# Sheet1.net
KiCad netlist of a schematic drawn in Altium Designer
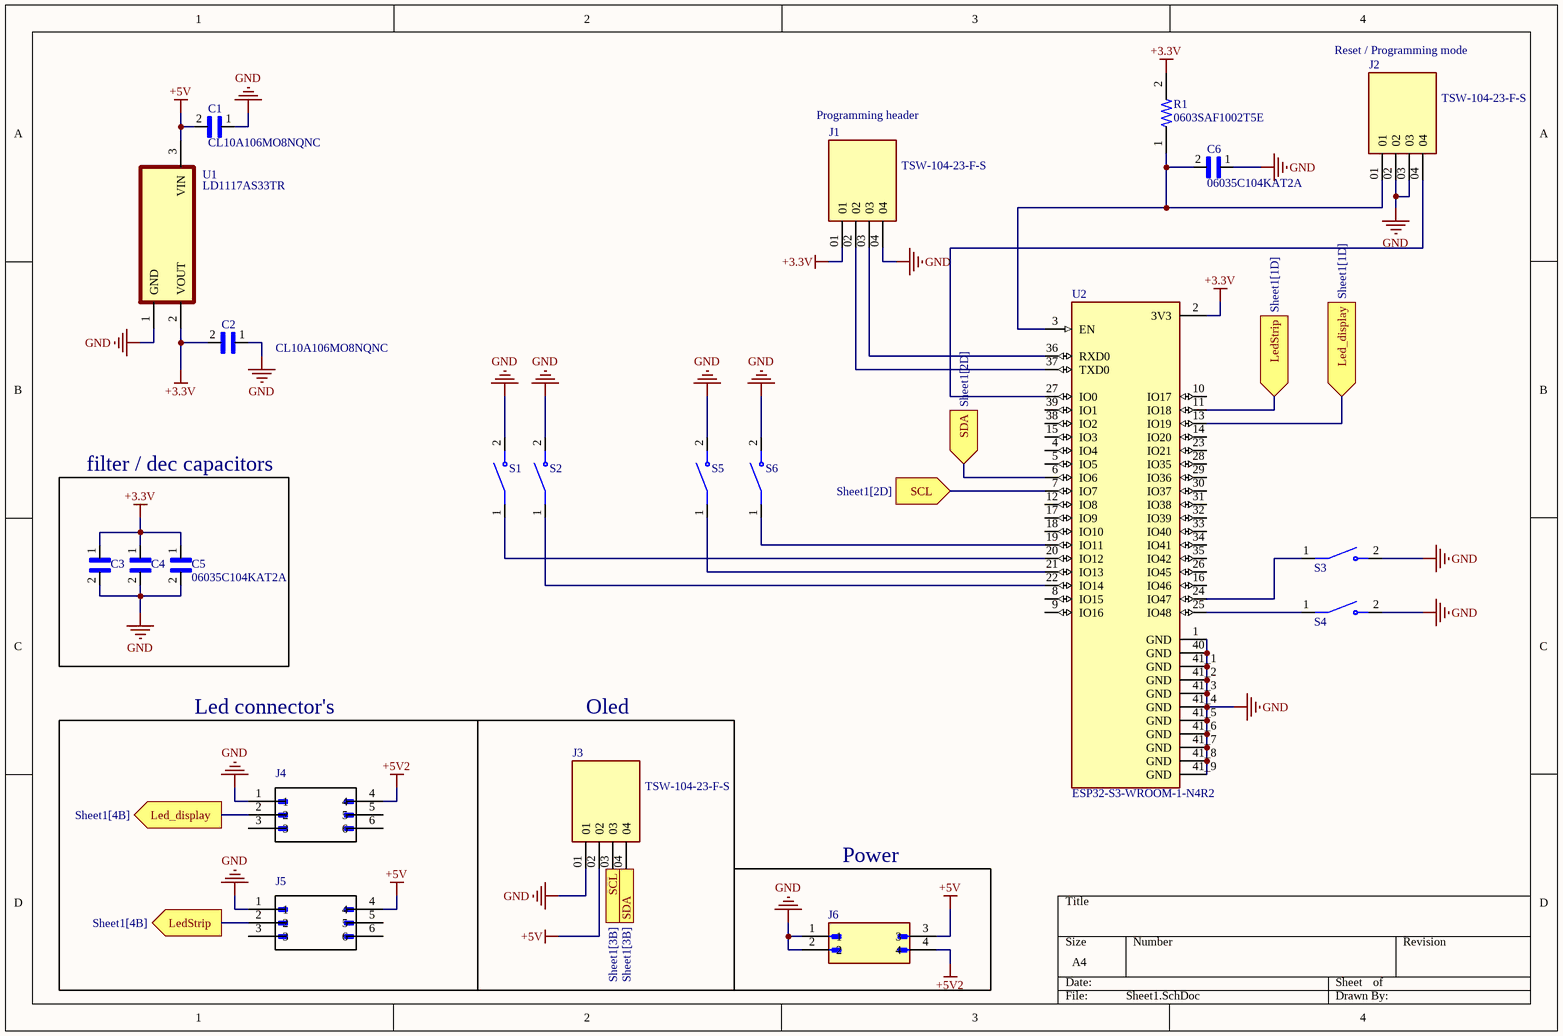
[diagram p0: Sheet1.SchDoc]

(export (version "E")
  (design (tool "Eeschema 10.0.6"))
  (components
    (comp (ref "C1")
      (value "CL10A106MO8NQNC")
      (footprint "CL10A106MO8NQNC:CAPC1608X90N")
      (description "Cap Ceramic 10uF 16V X5R 20% SMD 0603 85Â°C Paper T/R")
      (fields (field (name "MF") "{'manufacturer': u'Samsung Electro-Mechanics'}"))
      (libsource (lib "*") (part "CL10A106MO8NQNC"))
    )
    (comp (ref "C2")
      (value "CL10A106MO8NQNC")
      (footprint "CL10A106MO8NQNC:CAPC1608X90N")
      (description "Cap Ceramic 10uF 16V X5R 20% SMD 0603 85Â°C Paper T/R")
      (fields (field (name "MF") "{'manufacturer': u'Samsung Electro-Mechanics'}"))
      (libsource (lib "*") (part "CL10A106MO8NQNC"))
    )
    (comp (ref "C3")
      (value "06035C104KAT2A")
      (footprint "06035C104KAT2A:CAPC1608X90N")
      (fields (field (name "MF") "{'manufacturer': u'AVX'}"))
      (libsource (lib "*") (part "06035C104KAT2A"))
    )
    (comp (ref "C4")
      (value "06035C104KAT2A")
      (footprint "06035C104KAT2A:CAPC1608X90N")
      (fields (field (name "MF") "{'manufacturer': u'AVX'}"))
      (libsource (lib "*") (part "06035C104KAT2A"))
    )
    (comp (ref "C5")
      (value "06035C104KAT2A")
      (footprint "06035C104KAT2A:CAPC1608X90N")
      (fields (field (name "MF") "{'manufacturer': u'AVX'}"))
      (libsource (lib "*") (part "06035C104KAT2A"))
    )
    (comp (ref "C6")
      (value "06035C104KAT2A")
      (footprint "06035C104KAT2A:CAPC1608X90N")
      (fields (field (name "MF") "{'manufacturer': u'AVX'}"))
      (libsource (lib "") (part "06035C104KAT2A_1"))
    )
    (comp (ref "J1")
      (value "TSW-104-23-F-S")
      (footprint "TSW-104-23-F-S:SAMTEC_TSW-104-23-F-S")
      (fields (field (name "MF") "{'manufacturer': u'Samtec'}"))
      (libsource (lib "*") (part "TSW-104-23-F-S"))
    )
    (comp (ref "J2")
      (value "TSW-104-23-F-S")
      (footprint "TSW-104-23-F-S:SAMTEC_TSW-104-23-F-S")
      (fields (field (name "MF") "{'manufacturer': u'Samtec'}"))
      (libsource (lib "*") (part "TSW-104-23-F-S"))
    )
    (comp (ref "J3")
      (value "TSW-104-23-F-S")
      (footprint "TSW-104-23-F-S:SAMTEC_TSW-104-23-F-S")
      (fields (field (name "MF") "{'manufacturer': u'Samtec'}"))
      (libsource (lib "*") (part "TSW-104-23-F-S"))
    )
    (comp (ref "J4")
      (value "874270602")
      (footprint "*MOLEX_874270602")
      (libsource (lib "874270602") (part "874270602"))
    )
    (comp (ref "J5")
      (value "874270602")
      (footprint "*MOLEX_874270602")
      (libsource (lib "874270602") (part "874270602"))
    )
    (comp (ref "J6")
      (value "353180420")
      (footprint "*MOLEX_353180420")
      (description "Connector Header Through Hole, Right Angle 4 position 0.165in (4.20mm)")
      (fields (field (name "MF") "{'manufacturer': u'Molex'}"))
      (libsource (lib "*") (part "353180420"))
    )
    (comp (ref "R1")
      (value "0603SAF1002T5E")
      (footprint "RP73PF1J10KBTDF:RESC1608X50N")
      (description "0603 10k ohm")
      (fields
        (field (name "MF") "{'manufacturer': u'TE Connectivity'}")
        (field (name "MP") "RP73PF1J10KBTDF")
      )
      (libsource (lib "*") (part "RP73PF1J10KBTDF"))
    )
    (comp (ref "S1")
      (value "TL1107BF130WQ")
      (footprint "SW_MX_reversible")
      (fields (field (name "MF") "{'manufacturer': u'E-Switch'}"))
      (libsource (lib "TL1107BF130WQ") (part "TL1107BF130WQ"))
    )
    (comp (ref "S2")
      (value "TL1107BF130WQ")
      (footprint "SW_MX_reversible")
      (fields (field (name "MF") "{'manufacturer': u'E-Switch'}"))
      (libsource (lib "TL1107BF130WQ") (part "TL1107BF130WQ"))
    )
    (comp (ref "S3")
      (value "TL1107BF130WQ")
      (footprint "SW_MX_reversible")
      (fields (field (name "MF") "{'manufacturer': u'E-Switch'}"))
      (libsource (lib "TL1107BF130WQ") (part "TL1107BF130WQ"))
    )
    (comp (ref "S4")
      (value "TL1107BF130WQ")
      (footprint "SW_MX_reversible")
      (fields (field (name "MF") "{'manufacturer': u'E-Switch'}"))
      (libsource (lib "TL1107BF130WQ") (part "TL1107BF130WQ"))
    )
    (comp (ref "S5")
      (value "TL1107BF130WQ")
      (footprint "SW_MX_reversible")
      (fields (field (name "MF") "{'manufacturer': u'E-Switch'}"))
      (libsource (lib "TL1107BF130WQ") (part "TL1107BF130WQ"))
    )
    (comp (ref "S6")
      (value "TL1107BF130WQ")
      (footprint "SW_MX_reversible")
      (fields (field (name "MF") "{'manufacturer': u'E-Switch'}"))
      (libsource (lib "TL1107BF130WQ") (part "TL1107BF130WQ"))
    )
    (comp (ref "U1")
      (value "LD1117AS33TR")
      (footprint "LD1117AS33TR:SOT230P700X180-4N")
      (fields (field (name "MF") "{'manufacturer': u'STMicroelectronics'}"))
      (libsource (lib "*") (part "LD1117AS33TR"))
    )
    (comp (ref "U2")
      (value "ESP32-S3-WROOM-1-N4R2")
      (footprint "XCVR_ESP32-S3-WROOM-1-N4R2")
      (fields (field (name "MF") "{'manufacturer': u'Espressif Systems'}"))
      (libsource (lib "ESP32-S3-WROOM-1-N4R2") (part "ESP32-S3-WROOM-1-N4R2"))
    )
  )
  (nets
    (net (code "1") (name "+3.3V") (class "Default")
      (node (ref "C2") (pin "2") (pinfunction "2_2") (pintype "passive"))
      (node (ref "C3") (pin "1") (pinfunction "1_1") (pintype "passive"))
      (node (ref "C4") (pin "1") (pinfunction "1_1") (pintype "passive"))
      (node (ref "C5") (pin "1") (pinfunction "1_1") (pintype "passive"))
      (node (ref "J1") (pin "01") (pinfunction "01_01") (pintype "passive"))
      (node (ref "R1") (pin "2") (pinfunction "2_2") (pintype "passive"))
      (node (ref "U1") (pin "2") (pinfunction "VOUT_2") (pintype "power_in"))
      (node (ref "U2") (pin "2") (pinfunction "3V3_2") (pintype "power_in"))
    )
    (net (code "2") (name "+5V") (class "Default")
      (node (ref "C1") (pin "2") (pinfunction "2_2") (pintype "passive"))
      (node (ref "J3") (pin "02") (pinfunction "02_02") (pintype "passive"))
      (node (ref "J5") (pin "4") (pinfunction "4_4") (pintype "passive"))
      (node (ref "J6") (pin "3") (pinfunction "3_3") (pintype "passive"))
      (node (ref "U1") (pin "3") (pinfunction "VIN_3") (pintype "power_in"))
    )
    (net (code "3") (name "+5V2") (class "Default")
      (node (ref "J4") (pin "4") (pinfunction "4_4") (pintype "passive"))
      (node (ref "J6") (pin "4") (pinfunction "4_4") (pintype "passive"))
    )
    (net (code "4") (name "/LedStrip") (class "Default")
      (node (ref "J5") (pin "2") (pinfunction "2_2") (pintype "passive"))
      (node (ref "U2") (pin "11") (pinfunction "IO18_11") (pintype "bidirectional"))
    )
    (net (code "5") (name "/Led_display") (class "Default")
      (node (ref "J4") (pin "2") (pinfunction "2_2") (pintype "passive"))
      (node (ref "U2") (pin "13") (pinfunction "IO19_13") (pintype "bidirectional"))
    )
    (net (code "6") (name "/SCL") (class "Default")
      (node (ref "J3") (pin "03") (pinfunction "03_03") (pintype "passive"))
      (node (ref "U2") (pin "7") (pinfunction "IO7_7") (pintype "bidirectional"))
    )
    (net (code "7") (name "/SDA") (class "Default")
      (node (ref "J3") (pin "04") (pinfunction "04_04") (pintype "passive"))
      (node (ref "U2") (pin "6") (pinfunction "IO6_6") (pintype "bidirectional"))
    )
    (net (code "8") (name "GND") (class "Default")
      (node (ref "C1") (pin "1") (pinfunction "1_1") (pintype "passive"))
      (node (ref "C2") (pin "1") (pinfunction "1_1") (pintype "passive"))
      (node (ref "C3") (pin "2") (pinfunction "2_2") (pintype "passive"))
      (node (ref "C4") (pin "2") (pinfunction "2_2") (pintype "passive"))
      (node (ref "C5") (pin "2") (pinfunction "2_2") (pintype "passive"))
      (node (ref "C6") (pin "1") (pinfunction "1_1") (pintype "power_in"))
      (node (ref "J1") (pin "04") (pinfunction "04_04") (pintype "passive"))
      (node (ref "J2") (pin "02") (pinfunction "02_02") (pintype "passive"))
      (node (ref "J2") (pin "03") (pinfunction "03_03") (pintype "passive"))
      (node (ref "J3") (pin "01") (pinfunction "01_01") (pintype "passive"))
      (node (ref "J4") (pin "1") (pinfunction "1_1") (pintype "passive"))
      (node (ref "J5") (pin "1") (pinfunction "1_1") (pintype "passive"))
      (node (ref "J6") (pin "1") (pinfunction "1_1") (pintype "passive"))
      (node (ref "J6") (pin "2") (pinfunction "2_2") (pintype "passive"))
      (node (ref "S1") (pin "2") (pinfunction "2_2") (pintype "passive"))
      (node (ref "S2") (pin "2") (pinfunction "2_2") (pintype "passive"))
      (node (ref "S3") (pin "2") (pinfunction "2_2") (pintype "passive"))
      (node (ref "S4") (pin "2") (pinfunction "2_2") (pintype "passive"))
      (node (ref "S5") (pin "2") (pinfunction "2_2") (pintype "passive"))
      (node (ref "S6") (pin "2") (pinfunction "2_2") (pintype "passive"))
      (node (ref "U1") (pin "1") (pinfunction "GND_1") (pintype "power_in"))
      (node (ref "U2") (pin "1") (pinfunction "GND_1") (pintype "power_in"))
      (node (ref "U2") (pin "40") (pinfunction "GND_40") (pintype "power_in"))
      (node (ref "U2") (pin "41_1") (pinfunction "GND_41_1") (pintype "power_in"))
      (node (ref "U2") (pin "41_2") (pinfunction "GND_41_2") (pintype "power_in"))
      (node (ref "U2") (pin "41_3") (pinfunction "GND_41_3") (pintype "power_in"))
      (node (ref "U2") (pin "41_4") (pinfunction "GND_41_4") (pintype "power_in"))
      (node (ref "U2") (pin "41_5") (pinfunction "GND_41_5") (pintype "power_in"))
      (node (ref "U2") (pin "41_6") (pinfunction "GND_41_6") (pintype "power_in"))
      (node (ref "U2") (pin "41_7") (pinfunction "GND_41_7") (pintype "power_in"))
      (node (ref "U2") (pin "41_8") (pinfunction "GND_41_8") (pintype "power_in"))
      (node (ref "U2") (pin "41_9") (pinfunction "GND_41_9") (pintype "power_in"))
    )
    (net (code "9") (name "Net-(U2-EN)") (class "Default")
      (node (ref "C6") (pin "2") (pinfunction "2_2") (pintype "power_in"))
      (node (ref "J2") (pin "01") (pinfunction "01_01") (pintype "passive"))
      (node (ref "R1") (pin "1") (pinfunction "1_1") (pintype "passive"))
      (node (ref "U2") (pin "3") (pinfunction "EN_3") (pintype "input"))
    )
    (net (code "10") (name "Net-(U2-IO0)") (class "Default")
      (node (ref "J2") (pin "04") (pinfunction "04_04") (pintype "passive"))
      (node (ref "U2") (pin "27") (pinfunction "IO0_27") (pintype "bidirectional"))
    )
    (net (code "11") (name "Net-(U2-IO11)") (class "Default")
      (node (ref "S6") (pin "1") (pinfunction "1_1") (pintype "passive"))
      (node (ref "U2") (pin "19") (pinfunction "IO11_19") (pintype "bidirectional"))
    )
    (net (code "12") (name "Net-(U2-IO12)") (class "Default")
      (node (ref "S1") (pin "1") (pinfunction "1_1") (pintype "passive"))
      (node (ref "U2") (pin "20") (pinfunction "IO12_20") (pintype "bidirectional"))
    )
    (net (code "13") (name "Net-(U2-IO13)") (class "Default")
      (node (ref "S5") (pin "1") (pinfunction "1_1") (pintype "passive"))
      (node (ref "U2") (pin "21") (pinfunction "IO13_21") (pintype "bidirectional"))
    )
    (net (code "14") (name "Net-(U2-IO14)") (class "Default")
      (node (ref "S2") (pin "1") (pinfunction "1_1") (pintype "passive"))
      (node (ref "U2") (pin "22") (pinfunction "IO14_22") (pintype "bidirectional"))
    )
    (net (code "15") (name "Net-(U2-IO47)") (class "Default")
      (node (ref "S3") (pin "1") (pinfunction "1_1") (pintype "passive"))
      (node (ref "U2") (pin "24") (pinfunction "IO47_24") (pintype "bidirectional"))
    )
    (net (code "16") (name "Net-(U2-IO48)") (class "Default")
      (node (ref "S4") (pin "1") (pinfunction "1_1") (pintype "passive"))
      (node (ref "U2") (pin "25") (pinfunction "IO48_25") (pintype "bidirectional"))
    )
    (net (code "17") (name "Net-(U2-RXD0)") (class "Default")
      (node (ref "J1") (pin "03") (pinfunction "03_03") (pintype "passive"))
      (node (ref "U2") (pin "36") (pinfunction "RXD0_36") (pintype "bidirectional"))
    )
    (net (code "18") (name "Net-(U2-TXD0)") (class "Default")
      (node (ref "J1") (pin "02") (pinfunction "02_02") (pintype "passive"))
      (node (ref "U2") (pin "37") (pinfunction "TXD0_37") (pintype "bidirectional"))
    )
    (net (code "19") (name "unconnected-(J4-Pad3)") (class "Default")
      (node (ref "J4") (pin "3") (pinfunction "3_3") (pintype "passive"))
    )
    (net (code "20") (name "unconnected-(J4-Pad5)") (class "Default")
      (node (ref "J4") (pin "5") (pinfunction "5_5") (pintype "passive"))
    )
    (net (code "21") (name "unconnected-(J4-Pad6)") (class "Default")
      (node (ref "J4") (pin "6") (pinfunction "6_6") (pintype "passive"))
    )
    (net (code "22") (name "unconnected-(J5-Pad3)") (class "Default")
      (node (ref "J5") (pin "3") (pinfunction "3_3") (pintype "passive"))
    )
    (net (code "23") (name "unconnected-(J5-Pad5)") (class "Default")
      (node (ref "J5") (pin "5") (pinfunction "5_5") (pintype "passive"))
    )
    (net (code "24") (name "unconnected-(J5-Pad6)") (class "Default")
      (node (ref "J5") (pin "6") (pinfunction "6_6") (pintype "passive"))
    )
    (net (code "25") (name "unconnected-(U2-IO1-Pad39)") (class "Default")
      (node (ref "U2") (pin "39") (pinfunction "IO1_39") (pintype "bidirectional"))
    )
    (net (code "26") (name "unconnected-(U2-IO2-Pad38)") (class "Default")
      (node (ref "U2") (pin "38") (pinfunction "IO2_38") (pintype "bidirectional"))
    )
    (net (code "27") (name "unconnected-(U2-IO3-Pad15)") (class "Default")
      (node (ref "U2") (pin "15") (pinfunction "IO3_15") (pintype "bidirectional"))
    )
    (net (code "28") (name "unconnected-(U2-IO4-Pad4)") (class "Default")
      (node (ref "U2") (pin "4") (pinfunction "IO4_4") (pintype "bidirectional"))
    )
    (net (code "29") (name "unconnected-(U2-IO5-Pad5)") (class "Default")
      (node (ref "U2") (pin "5") (pinfunction "IO5_5") (pintype "bidirectional"))
    )
    (net (code "30") (name "unconnected-(U2-IO8-Pad12)") (class "Default")
      (node (ref "U2") (pin "12") (pinfunction "IO8_12") (pintype "bidirectional"))
    )
    (net (code "31") (name "unconnected-(U2-IO9-Pad17)") (class "Default")
      (node (ref "U2") (pin "17") (pinfunction "IO9_17") (pintype "bidirectional"))
    )
    (net (code "32") (name "unconnected-(U2-IO10-Pad18)") (class "Default")
      (node (ref "U2") (pin "18") (pinfunction "IO10_18") (pintype "bidirectional"))
    )
    (net (code "33") (name "unconnected-(U2-IO15-Pad8)") (class "Default")
      (node (ref "U2") (pin "8") (pinfunction "IO15_8") (pintype "bidirectional"))
    )
    (net (code "34") (name "unconnected-(U2-IO16-Pad9)") (class "Default")
      (node (ref "U2") (pin "9") (pinfunction "IO16_9") (pintype "bidirectional"))
    )
    (net (code "35") (name "unconnected-(U2-IO17-Pad10)") (class "Default")
      (node (ref "U2") (pin "10") (pinfunction "IO17_10") (pintype "bidirectional"))
    )
    (net (code "36") (name "unconnected-(U2-IO20-Pad14)") (class "Default")
      (node (ref "U2") (pin "14") (pinfunction "IO20_14") (pintype "bidirectional"))
    )
    (net (code "37") (name "unconnected-(U2-IO21-Pad23)") (class "Default")
      (node (ref "U2") (pin "23") (pinfunction "IO21_23") (pintype "bidirectional"))
    )
    (net (code "38") (name "unconnected-(U2-IO35-Pad28)") (class "Default")
      (node (ref "U2") (pin "28") (pinfunction "IO35_28") (pintype "bidirectional"))
    )
    (net (code "39") (name "unconnected-(U2-IO36-Pad29)") (class "Default")
      (node (ref "U2") (pin "29") (pinfunction "IO36_29") (pintype "bidirectional"))
    )
    (net (code "40") (name "unconnected-(U2-IO37-Pad30)") (class "Default")
      (node (ref "U2") (pin "30") (pinfunction "IO37_30") (pintype "bidirectional"))
    )
    (net (code "41") (name "unconnected-(U2-IO38-Pad31)") (class "Default")
      (node (ref "U2") (pin "31") (pinfunction "IO38_31") (pintype "bidirectional"))
    )
    (net (code "42") (name "unconnected-(U2-IO39-Pad32)") (class "Default")
      (node (ref "U2") (pin "32") (pinfunction "IO39_32") (pintype "bidirectional"))
    )
    (net (code "43") (name "unconnected-(U2-IO40-Pad33)") (class "Default")
      (node (ref "U2") (pin "33") (pinfunction "IO40_33") (pintype "bidirectional"))
    )
    (net (code "44") (name "unconnected-(U2-IO41-Pad34)") (class "Default")
      (node (ref "U2") (pin "34") (pinfunction "IO41_34") (pintype "bidirectional"))
    )
    (net (code "45") (name "unconnected-(U2-IO42-Pad35)") (class "Default")
      (node (ref "U2") (pin "35") (pinfunction "IO42_35") (pintype "bidirectional"))
    )
    (net (code "46") (name "unconnected-(U2-IO45-Pad26)") (class "Default")
      (node (ref "U2") (pin "26") (pinfunction "IO45_26") (pintype "bidirectional"))
    )
    (net (code "47") (name "unconnected-(U2-IO46-Pad16)") (class "Default")
      (node (ref "U2") (pin "16") (pinfunction "IO46_16") (pintype "bidirectional"))
    )
  )
)
